# LIN_Controller_Board.net
KiCad netlist of a schematic drawn in Altium Designer
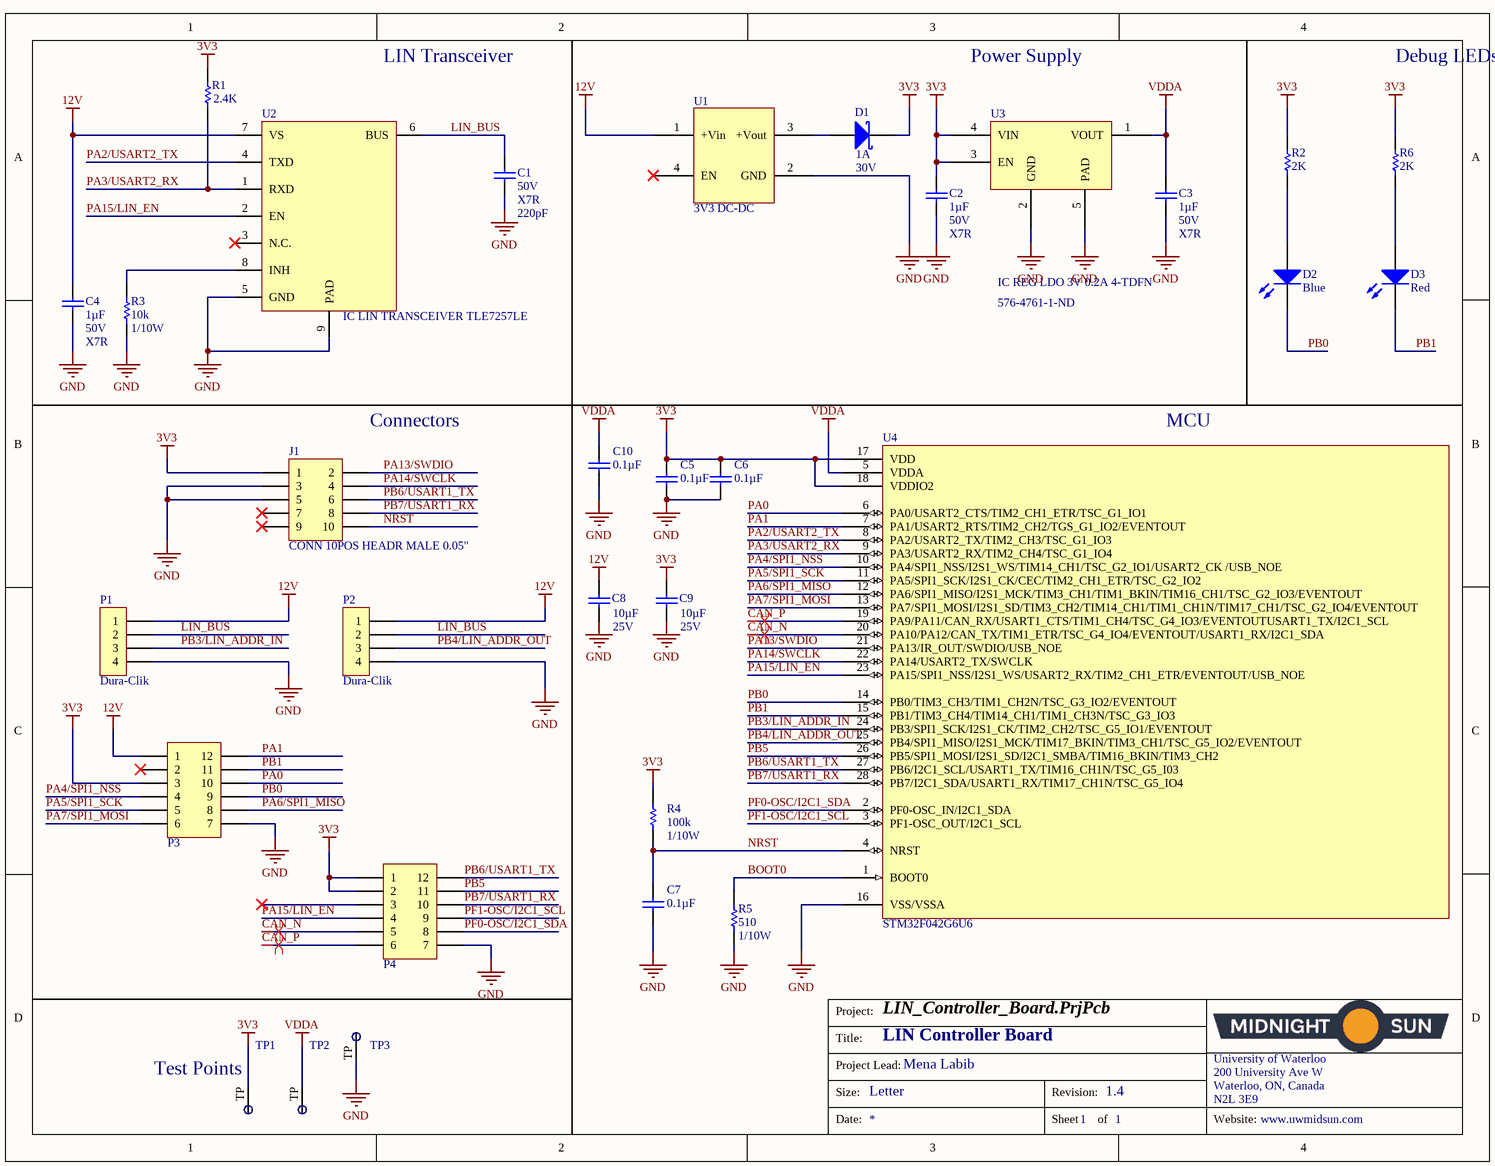
[diagram p0: LIN_Controller_Board.SchDoc]

(export (version "E")
  (design (tool "Eeschema 10.0.6"))
  (components
    (comp (ref "C1")
      (value "220pF")
      (footprint "CAP, 0603")
      (description "220pF ±5% 50V Ceramic Capacitor X7R 0603 (1608 Metric)")
      (fields
        (field (name "MANUFACTURER") "Murata Electronics North America")
        (field (name "MANUFACTURER PART NUMBER") "GRM188R71H221JA01D")
        (field (name "VOLTAGE - RATED") "50V")
        (field (name "TEMPERATURE COEFFICIENT") "X7R")
      )
      (libsource (lib "Schematic Diagrams") (part "CAP CER 220PF 50V 5% X7R 0603"))
    )
    (comp (ref "C2")
      (value "CAP CER 1UF 50V 10% X7R 0603")
      (footprint "CAP, 0603")
      (description "1µF ±10% 50V Ceramic Capacitor X7R 0603 (1608 Metric)")
      (fields
        (field (name "TOLERANCE") "±10%")
        (field (name "CAPACITANCE") "1µF")
        (field (name "VOLTAGE") "50V")
        (field (name "TEMPERATURE COEFFICIENT") "X7R")
      )
      (libsource (lib "Schematic Diagrams") (part "CAP CER 1UF 50V 10% X7R 0603"))
    )
    (comp (ref "C3")
      (value "CAP CER 1UF 50V 10% X7R 0603")
      (footprint "CAP, 0603")
      (description "1µF ±10% 50V Ceramic Capacitor X7R 0603 (1608 Metric)")
      (fields
        (field (name "TOLERANCE") "±10%")
        (field (name "CAPACITANCE") "1µF")
        (field (name "VOLTAGE") "50V")
        (field (name "TEMPERATURE COEFFICIENT") "X7R")
      )
      (libsource (lib "Schematic Diagrams") (part "CAP CER 1UF 50V 10% X7R 0603"))
    )
    (comp (ref "C4")
      (value "CAP CER 1UF 50V 10% X7R 0603")
      (footprint "CAP, 0603")
      (description "1µF ±10% 50V Ceramic Capacitor X7R 0603 (1608 Metric)")
      (fields
        (field (name "TOLERANCE") "±10%")
        (field (name "CAPACITANCE") "1µF")
        (field (name "VOLTAGE") "50V")
        (field (name "TEMPERATURE COEFFICIENT") "X7R")
      )
      (libsource (lib "Schematic Diagrams") (part "CAP CER 1UF 50V 10% X7R 0603"))
    )
    (comp (ref "C5")
      (value "CAP CER 0.1UF 50V 10% X7R 0603")
      (footprint "CAP, 0603")
      (description "0.10µF ±10% 50V Ceramic Capacitor X7R 0603 (1608 Metric)")
      (fields
        (field (name "VOLTAGE") "50V")
        (field (name "TOLERANCE") "±10%")
        (field (name "CAPACITANCE") "0.1µF")
      )
      (libsource (lib "Schematic Diagrams") (part "CAP CER 0.1UF 50V 10% X7R 0603"))
    )
    (comp (ref "C6")
      (value "CAP CER 0.1UF 50V 10% X7R 0603")
      (footprint "CAP, 0603")
      (description "0.10µF ±10% 50V Ceramic Capacitor X7R 0603 (1608 Metric)")
      (fields
        (field (name "VOLTAGE") "50V")
        (field (name "TOLERANCE") "±10%")
        (field (name "CAPACITANCE") "0.1µF")
      )
      (libsource (lib "Schematic Diagrams") (part "CAP CER 0.1UF 50V 10% X7R 0603"))
    )
    (comp (ref "C7")
      (value "CAP CER 0.1UF 50V 10% X7R 0603")
      (footprint "CAP, 0603")
      (description "0.10µF ±10% 50V Ceramic Capacitor X7R 0603 (1608 Metric)")
      (fields
        (field (name "VOLTAGE") "50V")
        (field (name "TOLERANCE") "±10%")
        (field (name "CAPACITANCE") "0.1µF")
      )
      (libsource (lib "Schematic Diagrams") (part "CAP CER 0.1UF 50V 10% X7R 0603"))
    )
    (comp (ref "C8")
      (value "CAP CER 10uF 25V 10% X5R 0805")
      (footprint "CAP, 0805")
      (description "10µF ±10% 25V Ceramic Capacitor X5R 0805 (2012 Metric)")
      (fields
        (field (name "MANUFACTURER") "Murata Electronics North America")
        (field (name "MANUFACTURER PART NUMBER") "GRM21BR61E106KA73L")
        (field (name "VOLTAGE - RATED") "25V")
        (field (name "CAPACITANCE") "10µF")
      )
      (libsource (lib "Schematic Diagrams") (part "CAP CER 10uF 25V 10% X5R 0805"))
    )
    (comp (ref "C9")
      (value "CAP CER 10uF 25V 10% X5R 0805")
      (footprint "CAP, 0805")
      (description "10µF ±10% 25V Ceramic Capacitor X5R 0805 (2012 Metric)")
      (fields
        (field (name "MANUFACTURER") "Murata Electronics North America")
        (field (name "MANUFACTURER PART NUMBER") "GRM21BR61E106KA73L")
        (field (name "VOLTAGE - RATED") "25V")
        (field (name "CAPACITANCE") "10µF")
      )
      (libsource (lib "Schematic Diagrams") (part "CAP CER 10uF 25V 10% X5R 0805"))
    )
    (comp (ref "C10")
      (value "CAP CER 0.1UF 50V 10% X7R 0603")
      (footprint "CAP, 0603")
      (description "0.10µF ±10% 50V Ceramic Capacitor X7R 0603 (1608 Metric)")
      (fields
        (field (name "VOLTAGE") "50V")
        (field (name "TOLERANCE") "±10%")
        (field (name "CAPACITANCE") "0.1µF")
      )
      (libsource (lib "Schematic Diagrams") (part "CAP CER 0.1UF 50V 10% X7R 0603"))
    )
    (comp (ref "D1")
      (value "DIODE SCHOTTKY 30V 1A POWERDI123")
      (footprint "DIODE SCHOTTKY 30V 1A POWERDI123")
      (description "Diode Schottky 30V 1A Surface Mount PowerDI™ 123")
      (fields
        (field (name "MANUFACTURER") "Diodes Incorporated")
        (field (name "MANUFACTURER PART NUMBER") "DFLS130L-7")
        (field (name "CURRENT - AVERAGE RECTIFIED (IO)") "1A")
        (field (name "VOLTAGE - DC REVERSE (VR) (MAX)") "30V")
      )
      (libsource (lib "Schematic Diagrams") (part "DIODE SCHOTTKY 30V 1A POWERDI123"))
    )
    (comp (ref "D2")
      (value "LED BLUE CLEAR 2.8V 0603")
      (footprint "LED_0603")
      (description "Blue 470nm LED Indication - Discrete 2.8V 0603 (1608 Metric)")
      (fields (field (name "COLOR") "Blue"))
      (libsource (lib "Schematic Diagrams") (part "LED BLUE CLEAR 2.8V 0603"))
    )
    (comp (ref "D3")
      (value "LED BLUE CLEAR 2.8V 0603")
      (footprint "LED_0603")
      (description "Blue 470nm LED Indication - Discrete 2.8V 0603 (1608 Metric)")
      (fields (field (name "COLOR") "Red"))
      (libsource (lib "Schematic Diagrams") (part "LED BLUE CLEAR 2.8V 0603"))
    )
    (comp (ref "J1")
      (value "CONN 10POS HEADR MALE 0.05\"")
      (footprint "CONN, 10POS 0.05\" Debug Header")
      (description "10 Positions Header Connector 0.050\" (1.27mm) Surface Mount Gold")
      (libsource (lib "Schematic Diagrams") (part "CONN 10POS HEADR MALE 0.05{dblquote}"))
    )
    (comp (ref "P1")
      (value "Dura-Clik")
      (footprint "CONN, 4POS DURA-CLIK VERT")
      (description "4 Positions Header Connector 0.079\" (2.00mm) Surface Mount Tin")
      (fields
        (field (name "MANUFACTURER") "Molex, LLC")
        (field (name "MANUFACTURER PART NUMBER") "5600200420")
      )
      (libsource (lib "Schematic Diagrams") (part "CONN 4POS DURA-CLIK 0.079{dblquote}"))
    )
    (comp (ref "P2")
      (value "Dura-Clik")
      (footprint "CONN, 4POS DURA-CLIK VERT")
      (description "4 Positions Header Connector 0.079\" (2.00mm) Surface Mount Tin")
      (fields
        (field (name "MANUFACTURER") "Molex, LLC")
        (field (name "MANUFACTURER PART NUMBER") "5600200420")
      )
      (libsource (lib "Schematic Diagrams") (part "CONN 4POS DURA-CLIK 0.079{dblquote}"))
    )
    (comp (ref "P3")
      (value "CONN 12POS HEADER MALE 0.1\"")
      (footprint "CONN, 12POS 0.100\" HEADER")
      (description "6 Positions Header Connector 0.100\" (2.54mm) Through Hole Gold or Gold, GXT")
      (fields
        (field (name "MANUFACTURER") "Amphenol FCI")
        (field (name "MANUFACTURER PART NUMBER") "67997-206HLF")
      )
      (libsource (lib "Schematic Diagrams") (part "CONN 12POS HEADER MALE 0.1{dblquote}"))
    )
    (comp (ref "P4")
      (value "CONN 12POS HEADER MALE 0.1\"")
      (footprint "CONN, 12POS 0.100\" HEADER")
      (description "6 Positions Header Connector 0.100\" (2.54mm) Through Hole Gold or Gold, GXT")
      (fields
        (field (name "MANUFACTURER") "Amphenol FCI")
        (field (name "MANUFACTURER PART NUMBER") "67997-206HLF")
      )
      (libsource (lib "Schematic Diagrams") (part "CONN 12POS HEADER MALE 0.1{dblquote}"))
    )
    (comp (ref "R1")
      (value "2.4K")
      (footprint "RES, 0603")
      (description "2.4 kOhms ±1% 0.1W, 1/10W Chip Resistor 0603 (1608 Metric) Moisture Resistant Thick Film")
      (fields
        (field (name "MANUFACTURER") "Yageo")
        (field (name "MANUFACTURER PART NUMBER") "RC0603FR-072K4L")
      )
      (libsource (lib "Schematic Diagrams") (part "RES 2.4K OHM 1% 1/10W 0603"))
    )
    (comp (ref "R2")
      (value "2K")
      (footprint "RES, 0603")
      (description "2k Ohm ±1% 0.1W, 1/10W Chip Resistor 0603 (1608 Metric) Moisture Resistant Thick Film")
      (fields
        (field (name "MANUFACTURER") "Yageo")
        (field (name "MANUFACTURER PART NUMBER") "RC0603FR-072KL")
      )
      (libsource (lib "Schematic Diagrams") (part "RES 2K OHM 1% 1/10W 0603"))
    )
    (comp (ref "R3")
      (value "RES 10K OHM 1% 1/10W 0603")
      (footprint "RES, 0603")
      (description "RES SMD 10K OHM 1% 1/10W 0603")
      (fields
        (field (name "TOLERANCE") "±1%")
        (field (name "RESISTANCE") "10k")
        (field (name "POWER") "1/10W")
      )
      (libsource (lib "Schematic Diagrams") (part "RES 10K OHM 1% 1/10W 0603"))
    )
    (comp (ref "R4")
      (value "RES 100K OHM 5% 1/8W 0603")
      (footprint "RES, 0603")
      (description "RES SMD 100K OHM 5% 1/10W 0603")
      (fields
        (field (name "TOLERANCE") "±5%")
        (field (name "RESISTANCE") "100k")
        (field (name "POWER") "1/10W")
      )
      (libsource (lib "Schematic Diagrams") (part "RES 100K OHM 5% 1/8W 0603"))
    )
    (comp (ref "R5")
      (value "RES 510 OHM 5% 1/10W 0603")
      (footprint "RES, 0603")
      (description "RES SMD 510 OHM 5% 1/10W 0603")
      (fields
        (field (name "TOLERANCE") "±5%")
        (field (name "RESISTANCE") "510")
        (field (name "POWER") "1/10W")
      )
      (libsource (lib "Schematic Diagrams") (part "RES 510 OHM 5% 1/10W 0603"))
    )
    (comp (ref "R6")
      (value "2K")
      (footprint "RES, 0603")
      (description "2k Ohm ±1% 0.1W, 1/10W Chip Resistor 0603 (1608 Metric) Moisture Resistant Thick Film")
      (fields
        (field (name "MANUFACTURER") "Yageo")
        (field (name "MANUFACTURER PART NUMBER") "RC0603FR-072KL")
      )
      (libsource (lib "Schematic Diagrams") (part "RES 2K OHM 1% 1/10W 0603"))
    )
    (comp (ref "TP1")
      (value "Test Point")
      (footprint "Test Point")
      (libsource (lib "Schematic Diagrams") (part "Test Point"))
    )
    (comp (ref "TP2")
      (value "Test Point")
      (footprint "Test Point")
      (libsource (lib "Schematic Diagrams") (part "Test Point"))
    )
    (comp (ref "TP3")
      (value "Test Point")
      (footprint "Test Point")
      (libsource (lib "Schematic Diagrams") (part "Test Point"))
    )
    (comp (ref "U1")
      (value "IC DCDC 3.3V 0.5A 4-SMD")
      (footprint "IC DCDC 3.3V 0.5A 4-SMD")
      (description "Non-isolated PoL DC-DC Module 3.3V Output 0.5A 5-36V Input")
      (fields
        (field (name "MANUFACTURER") "Recom Power")
        (field (name "MANUFACTURER PART NUMBER") "ROF-78E3.3-0.5SMD-R")
      )
      (libsource (lib "Schematic Diagrams") (part "IC DCDC 3.3V 0.5A 4-SMD"))
    )
    (comp (ref "U2")
      (value "IC LIN TRANSCEIVER TLE7257LE")
      (footprint "IC LIN TRANSCEIVER TLE7257LE")
      (description "1/1 Transceiver LIN PG-TSON-8")
      (fields
        (field (name "MANUFACTURER") "Infineon Technologies")
        (field (name "MANUFACTURER PART NUMBER") "TLE7257LEXUMA1")
      )
      (libsource (lib "Schematic Diagrams") (part "IC LIN TRANSCEIVER TLE7257LE"))
    )
    (comp (ref "U3")
      (value "IC REG LDO 3V 0.2A 4-TDFN")
      (footprint "IC REG LDO 3V 0.2A 4-TDFN")
      (fields
        (field (name "MANUFACTURER") "Microchip Technology")
        (field (name "MANUFACTURER PART NUMBER") "MIC94310-PYMT-TR")
        (field (name "SUPPLIER PART NUMBER 1") "576-4761-1-ND")
      )
      (libsource (lib "Schematic Diagrams") (part "IC REG LDO 3V 0.2A 4-TDFN"))
    )
    (comp (ref "U4")
      (value "IC MCU 32BIT 32KB FLASH 28UFQFPN")
      (footprint "IC MCU 32BIT 32KB FLASH 28UFQFPN")
      (description "ARM® Cortex®-M0 STM32F0 Microcontroller IC 32-Bit 48MHz 32KB (32K x 8) FLASH 28-UFQFPN (4x4)")
      (fields
        (field (name "MANUFACTURER") "STMicroelectronics")
        (field (name "MANUFACTURER PART NUMBER") "STM32F042G6U6")
      )
      (libsource (lib "Schematic Diagrams") (part "IC MCU 32BIT 32KB FLASH 28UFQFPN"))
    )
  )
  (nets
    (net (code "1") (name "/BOOT0") (class "Default")
      (node (ref "R5") (pin "2") (pinfunction "2_2") (pintype "passive"))
      (node (ref "U4") (pin "1") (pinfunction "BOOT0_1") (pintype "input"))
    )
    (net (code "2") (name "/CAN_N") (class "Default")
      (node (ref "P4") (pin "5") (pinfunction "5_5") (pintype "passive"))
      (node (ref "U4") (pin "20") (pinfunction "PA10/PA12/CAN_TX/TIM1_ETR/TSC_G4_IO4/EVENTOUT/USART1_RX/I2C1_SDA_20") (pintype "bidirectional"))
    )
    (net (code "3") (name "/CAN_P") (class "Default")
      (node (ref "P4") (pin "6") (pinfunction "6_6") (pintype "passive"))
      (node (ref "U4") (pin "19") (pinfunction "PA9/PA11/CAN_RX/USART1_CTS/TIM1_CH4/TSC_G4_IO3/EVENTOUTUSART1_TX/I2C1_SCL_19") (pintype "bidirectional"))
    )
    (net (code "4") (name "/LIN_BUS") (class "Default")
      (node (ref "C1") (pin "1") (pinfunction "1_1") (pintype "passive"))
      (node (ref "P1") (pin "2") (pinfunction "2_2") (pintype "passive"))
      (node (ref "P2") (pin "2") (pinfunction "2_2") (pintype "passive"))
      (node (ref "U2") (pin "6") (pinfunction "BUS_6") (pintype "passive"))
    )
    (net (code "5") (name "/NRST") (class "Default")
      (node (ref "C7") (pin "2") (pinfunction "2_2") (pintype "passive"))
      (node (ref "J1") (pin "10") (pinfunction "10_10") (pintype "passive"))
      (node (ref "R4") (pin "1") (pinfunction "1_1") (pintype "passive"))
      (node (ref "U4") (pin "4") (pinfunction "NRST_4") (pintype "bidirectional"))
    )
    (net (code "6") (name "/PA0") (class "Default")
      (node (ref "P3") (pin "10") (pinfunction "10_10") (pintype "passive"))
      (node (ref "U4") (pin "6") (pinfunction "PA0/USART2_CTS/TIM2_CH1_ETR/TSC_G1_IO1_6") (pintype "bidirectional"))
    )
    (net (code "7") (name "/PA1") (class "Default")
      (node (ref "P3") (pin "12") (pinfunction "12_12") (pintype "passive"))
      (node (ref "U4") (pin "7") (pinfunction "PA1/USART2_RTS/TIM2_CH2/TGS_G1_IO2/EVENTOUT_7") (pintype "bidirectional"))
    )
    (net (code "8") (name "/PA2{slash}USART2_TX") (class "Default")
      (node (ref "U2") (pin "4") (pinfunction "TXD_4") (pintype "passive"))
      (node (ref "U4") (pin "8") (pinfunction "PA2/USART2_TX/TIM2_CH3/TSC_G1_IO3_8") (pintype "bidirectional"))
    )
    (net (code "9") (name "/PA3{slash}USART2_RX") (class "Default")
      (node (ref "R1") (pin "2") (pinfunction "2_2") (pintype "passive"))
      (node (ref "U2") (pin "1") (pinfunction "RXD_1") (pintype "passive"))
      (node (ref "U4") (pin "9") (pinfunction "PA3/USART2_RX/TIM2_CH4/TSC_G1_IO4_9") (pintype "bidirectional"))
    )
    (net (code "10") (name "/PA4{slash}SPI1_NSS") (class "Default")
      (node (ref "P3") (pin "4") (pinfunction "4_4") (pintype "passive"))
      (node (ref "U4") (pin "10") (pinfunction "PA4/SPI1_NSS/I2S1_WS/TIM14_CH1/TSC_G2_IO1/USART2_CK_/USB_NOE_10") (pintype "bidirectional"))
    )
    (net (code "11") (name "/PA5{slash}SPI1_SCK") (class "Default")
      (node (ref "P3") (pin "5") (pinfunction "5_5") (pintype "passive"))
      (node (ref "U4") (pin "11") (pinfunction "PA5/SPI1_SCK/I2S1_CK/CEC/TIM2_CH1_ETR/TSC_G2_IO2_11") (pintype "bidirectional"))
    )
    (net (code "12") (name "/PA6{slash}SPI1_MISO") (class "Default")
      (node (ref "P3") (pin "8") (pinfunction "8_8") (pintype "passive"))
      (node (ref "U4") (pin "12") (pinfunction "PA6/SPI1_MISO/I2S1_MCK/TIM3_CH1/TIM1_BKIN/TIM16_CH1/TSC_G2_IO3/EVENTOUT_12") (pintype "bidirectional"))
    )
    (net (code "13") (name "/PA7{slash}SPI1_MOSI") (class "Default")
      (node (ref "P3") (pin "6") (pinfunction "6_6") (pintype "passive"))
      (node (ref "U4") (pin "13") (pinfunction "PA7/SPI1_MOSI/I2S1_SD/TIM3_CH2/TIM14_CH1/TIM1_CH1N/TIM17_CH1/TSC_G2_IO4/EVENTOUT_13") (pintype "bidirectional"))
    )
    (net (code "14") (name "/PA13{slash}SWDIO") (class "Default")
      (node (ref "J1") (pin "2") (pinfunction "2_2") (pintype "passive"))
      (node (ref "U4") (pin "21") (pinfunction "PA13/IR_OUT/SWDIO/USB_NOE_21") (pintype "bidirectional"))
    )
    (net (code "15") (name "/PA14{slash}SWCLK") (class "Default")
      (node (ref "J1") (pin "4") (pinfunction "4_4") (pintype "passive"))
      (node (ref "U4") (pin "22") (pinfunction "PA14/USART2_TX/SWCLK_22") (pintype "bidirectional"))
    )
    (net (code "16") (name "/PA15{slash}LIN_EN") (class "Default")
      (node (ref "P4") (pin "4") (pinfunction "4_4") (pintype "passive"))
      (node (ref "U2") (pin "2") (pinfunction "EN_2") (pintype "passive"))
      (node (ref "U4") (pin "23") (pinfunction "PA15/SPI1_NSS/I2S1_WS/USART2_RX/TIM2_CH1_ETR/EVENTOUT/USB_NOE_23") (pintype "bidirectional"))
    )
    (net (code "17") (name "/PB0") (class "Default")
      (node (ref "D2") (pin "2") (pinfunction "K_2") (pintype "passive"))
      (node (ref "P3") (pin "9") (pinfunction "9_9") (pintype "passive"))
      (node (ref "U4") (pin "14") (pinfunction "PB0/TIM3_CH3/TIM1_CH2N/TSC_G3_IO2/EVENTOUT_14") (pintype "bidirectional"))
    )
    (net (code "18") (name "/PB1") (class "Default")
      (node (ref "D3") (pin "2") (pinfunction "K_2") (pintype "passive"))
      (node (ref "P3") (pin "11") (pinfunction "11_11") (pintype "passive"))
      (node (ref "U4") (pin "15") (pinfunction "PB1/TIM3_CH4/TIM14_CH1/TIM1_CH3N/TSC_G3_IO3_15") (pintype "bidirectional"))
    )
    (net (code "19") (name "/PB3{slash}LIN_ADDR_IN") (class "Default")
      (node (ref "P1") (pin "3") (pinfunction "3_3") (pintype "passive"))
      (node (ref "U4") (pin "24") (pinfunction "PB3/SPI1_SCK/I2S1_CK/TIM2_CH2/TSC_G5_IO1/EVENTOUT_24") (pintype "bidirectional"))
    )
    (net (code "20") (name "/PB4{slash}LIN_ADDR_OUT") (class "Default")
      (node (ref "P2") (pin "3") (pinfunction "3_3") (pintype "passive"))
      (node (ref "U4") (pin "25") (pinfunction "PB4/SPI1_MISO/I2S1_MCK/TIM17_BKIN/TIM3_CH1/TSC_G5_IO2/EVENTOUT_25") (pintype "bidirectional"))
    )
    (net (code "21") (name "/PB5") (class "Default")
      (node (ref "P4") (pin "11") (pinfunction "11_11") (pintype "passive"))
      (node (ref "U4") (pin "26") (pinfunction "PB5/SPI1_MOSI/I2S1_SD/I2C1_SMBA/TIM16_BKIN/TIM3_CH2_26") (pintype "bidirectional"))
    )
    (net (code "22") (name "/PB6{slash}USART1_TX") (class "Default")
      (node (ref "J1") (pin "6") (pinfunction "6_6") (pintype "passive"))
      (node (ref "P4") (pin "12") (pinfunction "12_12") (pintype "passive"))
      (node (ref "U4") (pin "27") (pinfunction "PB6/I2C1_SCL/USART1_TX/TIM16_CH1N/TSC_G5_I03_27") (pintype "bidirectional"))
    )
    (net (code "23") (name "/PB7{slash}USART1_RX") (class "Default")
      (node (ref "J1") (pin "8") (pinfunction "8_8") (pintype "passive"))
      (node (ref "P4") (pin "10") (pinfunction "10_10") (pintype "passive"))
      (node (ref "U4") (pin "28") (pinfunction "PB7/I2C1_SDA/USART1_RX/TIM17_CH1N/TSC_G5_IO4_28") (pintype "bidirectional"))
    )
    (net (code "24") (name "/PF0-OSC{slash}I2C1_SDA") (class "Default")
      (node (ref "P4") (pin "8") (pinfunction "8_8") (pintype "passive"))
      (node (ref "U4") (pin "2") (pinfunction "PF0-OSC_IN/I2C1_SDA_2") (pintype "bidirectional"))
    )
    (net (code "25") (name "/PF1-OSC{slash}I2C1_SCL") (class "Default")
      (node (ref "P4") (pin "9") (pinfunction "9_9") (pintype "passive"))
      (node (ref "U4") (pin "3") (pinfunction "PF1-OSC_OUT/I2C1_SCL_3") (pintype "bidirectional"))
    )
    (net (code "26") (name "3V3") (class "Default")
      (node (ref "C2") (pin "1") (pinfunction "1_1") (pintype "passive"))
      (node (ref "C5") (pin "2") (pinfunction "2_2") (pintype "passive"))
      (node (ref "C6") (pin "2") (pinfunction "2_2") (pintype "passive"))
      (node (ref "C9") (pin "1") (pinfunction "1_1") (pintype "passive"))
      (node (ref "D1") (pin "2") (pinfunction "K_2") (pintype "passive"))
      (node (ref "J1") (pin "1") (pinfunction "1_1") (pintype "passive"))
      (node (ref "P3") (pin "3") (pinfunction "3_3") (pintype "passive"))
      (node (ref "P4") (pin "1") (pinfunction "1_1") (pintype "passive"))
      (node (ref "P4") (pin "2") (pinfunction "2_2") (pintype "passive"))
      (node (ref "R1") (pin "1") (pinfunction "1_1") (pintype "passive"))
      (node (ref "R2") (pin "1") (pinfunction "1_1") (pintype "passive"))
      (node (ref "R4") (pin "2") (pinfunction "2_2") (pintype "passive"))
      (node (ref "R6") (pin "1") (pinfunction "1_1") (pintype "passive"))
      (node (ref "TP1") (pin "TP") (pinfunction "1_TP") (pintype "passive"))
      (node (ref "U3") (pin "3") (pinfunction "EN_3") (pintype "passive"))
      (node (ref "U3") (pin "4") (pinfunction "VIN_4") (pintype "passive"))
      (node (ref "U4") (pin "17") (pinfunction "VDD_17") (pintype "passive"))
      (node (ref "U4") (pin "18") (pinfunction "VDDIO2_18") (pintype "passive"))
    )
    (net (code "27") (name "12V") (class "Default")
      (node (ref "C4") (pin "1") (pinfunction "1_1") (pintype "passive"))
      (node (ref "C8") (pin "1") (pinfunction "1_1") (pintype "passive"))
      (node (ref "P1") (pin "1") (pinfunction "1_1") (pintype "passive"))
      (node (ref "P2") (pin "1") (pinfunction "1_1") (pintype "passive"))
      (node (ref "P3") (pin "1") (pinfunction "1_1") (pintype "passive"))
      (node (ref "U1") (pin "1") (pinfunction "+Vin_1") (pintype "passive"))
      (node (ref "U2") (pin "7") (pinfunction "VS_7") (pintype "passive"))
    )
    (net (code "28") (name "GND") (class "Default")
      (node (ref "C1") (pin "2") (pinfunction "2_2") (pintype "passive"))
      (node (ref "C10") (pin "1") (pinfunction "1_1") (pintype "passive"))
      (node (ref "C2") (pin "2") (pinfunction "2_2") (pintype "passive"))
      (node (ref "C3") (pin "2") (pinfunction "2_2") (pintype "passive"))
      (node (ref "C4") (pin "2") (pinfunction "2_2") (pintype "passive"))
      (node (ref "C5") (pin "1") (pinfunction "1_1") (pintype "passive"))
      (node (ref "C6") (pin "1") (pinfunction "1_1") (pintype "passive"))
      (node (ref "C7") (pin "1") (pinfunction "1_1") (pintype "passive"))
      (node (ref "C8") (pin "2") (pinfunction "2_2") (pintype "passive"))
      (node (ref "C9") (pin "2") (pinfunction "2_2") (pintype "passive"))
      (node (ref "J1") (pin "3") (pinfunction "3_3") (pintype "passive"))
      (node (ref "J1") (pin "5") (pinfunction "5_5") (pintype "passive"))
      (node (ref "P1") (pin "4") (pinfunction "4_4") (pintype "passive"))
      (node (ref "P2") (pin "4") (pinfunction "4_4") (pintype "passive"))
      (node (ref "P3") (pin "7") (pinfunction "7_7") (pintype "passive"))
      (node (ref "P4") (pin "7") (pinfunction "7_7") (pintype "passive"))
      (node (ref "R3") (pin "2") (pinfunction "2_2") (pintype "passive"))
      (node (ref "R5") (pin "1") (pinfunction "1_1") (pintype "passive"))
      (node (ref "TP3") (pin "TP") (pinfunction "1_TP") (pintype "passive"))
      (node (ref "U1") (pin "2") (pinfunction "GND_2") (pintype "passive"))
      (node (ref "U2") (pin "5") (pinfunction "GND_5") (pintype "passive"))
      (node (ref "U2") (pin "9") (pinfunction "PAD_9") (pintype "passive"))
      (node (ref "U3") (pin "2") (pinfunction "GND_2") (pintype "passive"))
      (node (ref "U3") (pin "5") (pinfunction "PAD_5") (pintype "passive"))
      (node (ref "U4") (pin "16") (pinfunction "VSS/VSSA_16") (pintype "passive"))
    )
    (net (code "29") (name "Net-(D1-A)") (class "Default")
      (node (ref "D1") (pin "1") (pinfunction "A_1") (pintype "passive"))
      (node (ref "U1") (pin "3") (pinfunction "+Vout_3") (pintype "passive"))
    )
    (net (code "30") (name "Net-(D2-A)") (class "Default")
      (node (ref "D2") (pin "1") (pinfunction "A_1") (pintype "passive"))
      (node (ref "R2") (pin "2") (pinfunction "2_2") (pintype "passive"))
    )
    (net (code "31") (name "Net-(D3-A)") (class "Default")
      (node (ref "D3") (pin "1") (pinfunction "A_1") (pintype "passive"))
      (node (ref "R6") (pin "2") (pinfunction "2_2") (pintype "passive"))
    )
    (net (code "32") (name "Net-(U2-INH)") (class "Default")
      (node (ref "R3") (pin "1") (pinfunction "1_1") (pintype "passive"))
      (node (ref "U2") (pin "8") (pinfunction "INH_8") (pintype "passive"))
    )
    (net (code "33") (name "VDDA") (class "Default")
      (node (ref "C10") (pin "2") (pinfunction "2_2") (pintype "passive"))
      (node (ref "C3") (pin "1") (pinfunction "1_1") (pintype "passive"))
      (node (ref "TP2") (pin "TP") (pinfunction "1_TP") (pintype "passive"))
      (node (ref "U3") (pin "1") (pinfunction "VOUT_1") (pintype "passive"))
      (node (ref "U4") (pin "5") (pinfunction "VDDA_5") (pintype "passive"))
    )
    (net (code "34") (name "unconnected-(J1-Pad7)") (class "Default")
      (node (ref "J1") (pin "7") (pinfunction "7_7") (pintype "passive+no_connect"))
    )
    (net (code "35") (name "unconnected-(J1-Pad9)") (class "Default")
      (node (ref "J1") (pin "9") (pinfunction "9_9") (pintype "passive+no_connect"))
    )
    (net (code "36") (name "unconnected-(P3-Pad2)") (class "Default")
      (node (ref "P3") (pin "2") (pinfunction "2_2") (pintype "passive+no_connect"))
    )
    (net (code "37") (name "unconnected-(P4-Pad3)") (class "Default")
      (node (ref "P4") (pin "3") (pinfunction "3_3") (pintype "passive+no_connect"))
    )
    (net (code "38") (name "unconnected-(U1-EN-Pad4)") (class "Default")
      (node (ref "U1") (pin "4") (pinfunction "EN_4") (pintype "passive+no_connect"))
    )
    (net (code "39") (name "unconnected-(U2-N.C.-Pad3)") (class "Default")
      (node (ref "U2") (pin "3") (pinfunction "N.C._3") (pintype "passive+no_connect"))
    )
  )
)
